# SWITCHES.net
KiCad netlist of a schematic drawn in Altium Designer
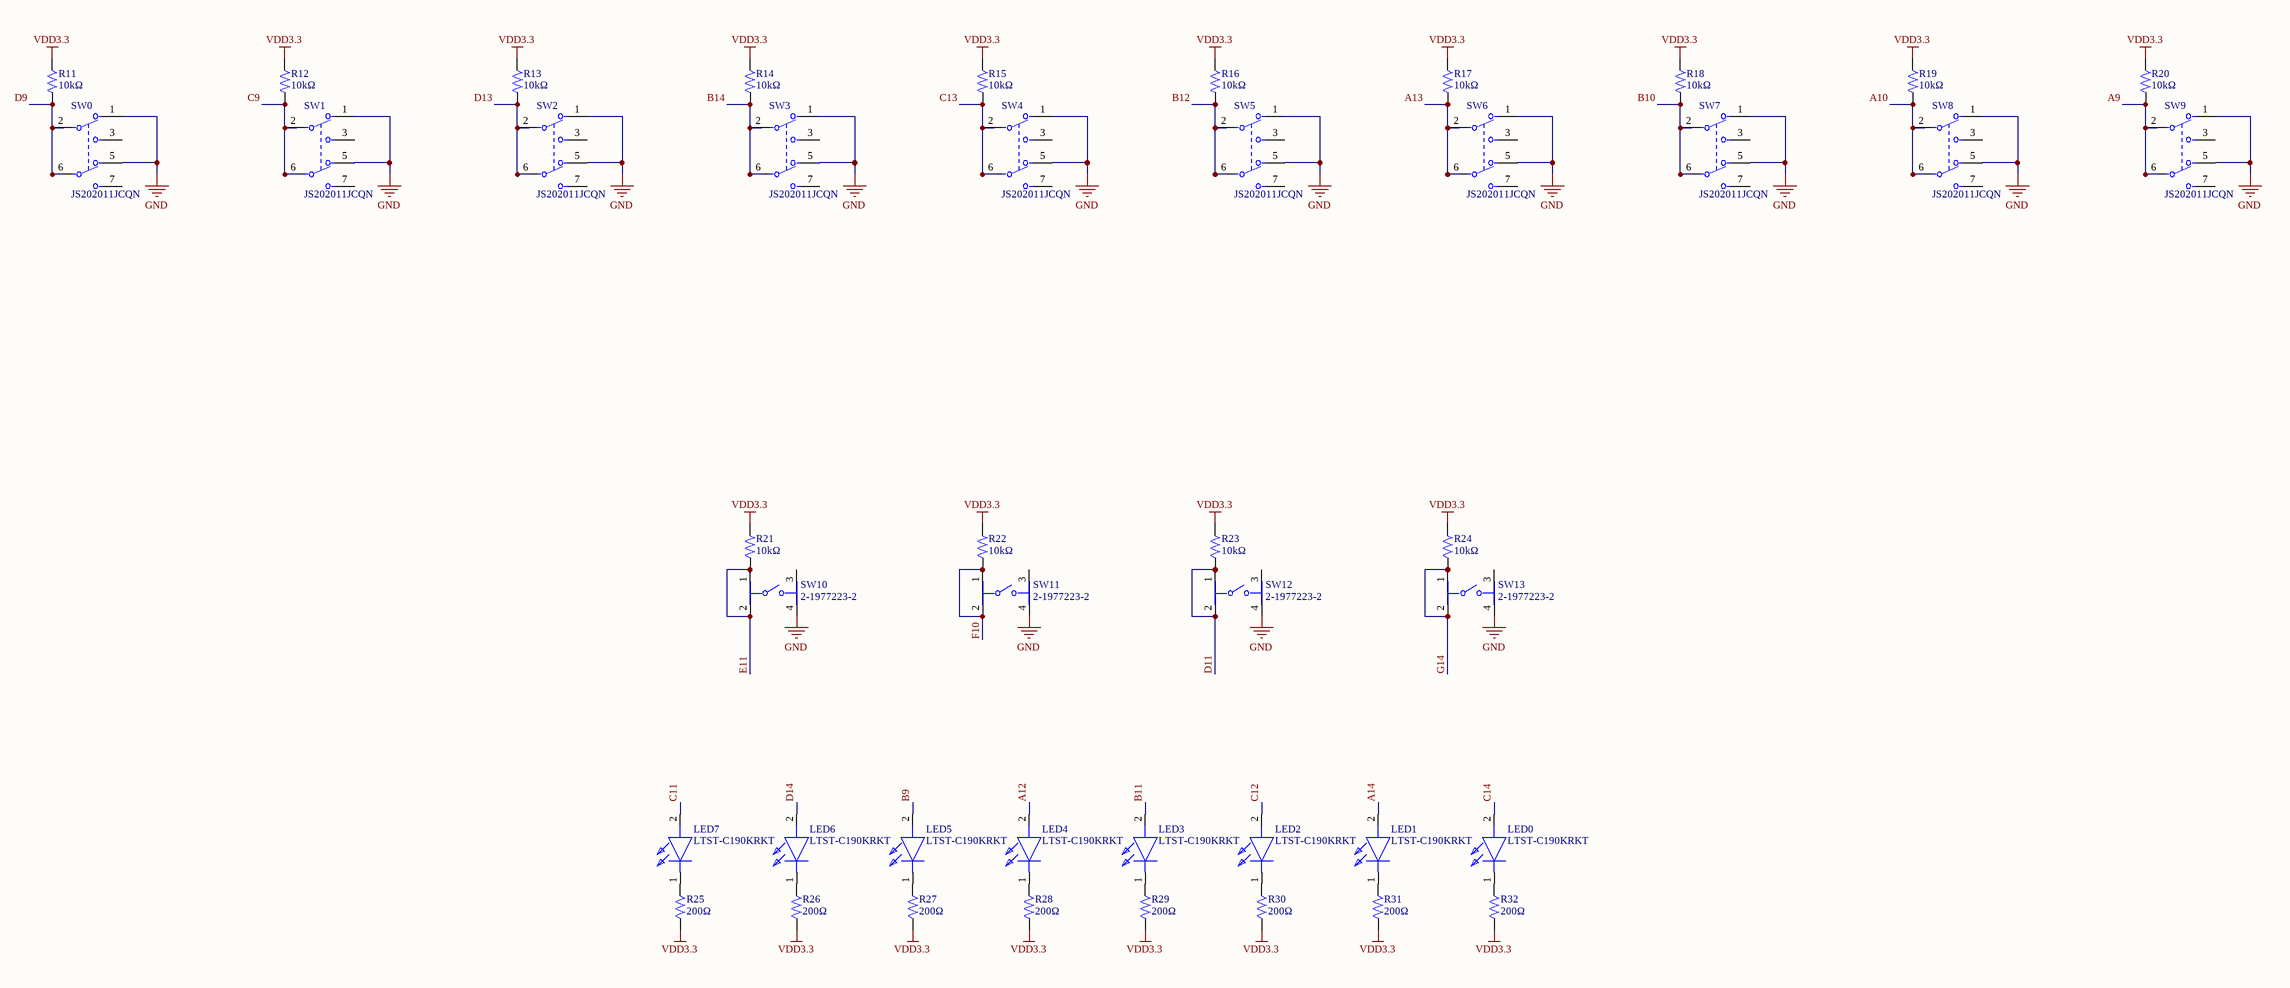
[diagram p0: SWITCHES.SchDoc]

(export (version "E")
  (design (tool "Eeschema 10.0.6"))
  (components
    (comp (ref "LED0")
      (value "LTST-C190KRKT")
      (footprint "SamacSys:LEDC1608X80N")
      (description "LED")
      (fields (field (name "MOUSER PART NUMBER") "859-LTST-C190KRKT"))
      (libsource (lib "*") (part "LTST-C190KRKT"))
    )
    (comp (ref "LED1")
      (value "LTST-C190KRKT")
      (footprint "SamacSys:LEDC1608X80N")
      (description "LED")
      (fields (field (name "MOUSER PART NUMBER") "859-LTST-C190KRKT"))
      (libsource (lib "*") (part "LTST-C190KRKT"))
    )
    (comp (ref "LED2")
      (value "LTST-C190KRKT")
      (footprint "SamacSys:LEDC1608X80N")
      (description "LED")
      (fields (field (name "MOUSER PART NUMBER") "859-LTST-C190KRKT"))
      (libsource (lib "*") (part "LTST-C190KRKT"))
    )
    (comp (ref "LED3")
      (value "LTST-C190KRKT")
      (footprint "SamacSys:LEDC1608X80N")
      (description "LED")
      (fields (field (name "MOUSER PART NUMBER") "859-LTST-C190KRKT"))
      (libsource (lib "*") (part "LTST-C190KRKT"))
    )
    (comp (ref "LED4")
      (value "LTST-C190KRKT")
      (footprint "SamacSys:LEDC1608X80N")
      (description "LED")
      (fields (field (name "MOUSER PART NUMBER") "859-LTST-C190KRKT"))
      (libsource (lib "*") (part "LTST-C190KRKT"))
    )
    (comp (ref "LED5")
      (value "LTST-C190KRKT")
      (footprint "SamacSys:LEDC1608X80N")
      (description "LED")
      (fields (field (name "MOUSER PART NUMBER") "859-LTST-C190KRKT"))
      (libsource (lib "*") (part "LTST-C190KRKT"))
    )
    (comp (ref "LED6")
      (value "LTST-C190KRKT")
      (footprint "SamacSys:LEDC1608X80N")
      (description "LED")
      (fields (field (name "MOUSER PART NUMBER") "859-LTST-C190KRKT"))
      (libsource (lib "*") (part "LTST-C190KRKT"))
    )
    (comp (ref "LED7")
      (value "LTST-C190KRKT")
      (footprint "SamacSys:LEDC1608X80N")
      (description "LED")
      (fields (field (name "MOUSER PART NUMBER") "859-LTST-C190KRKT"))
      (libsource (lib "*") (part "LTST-C190KRKT"))
    )
    (comp (ref "R11")
      (value "0603WAF1002T5E")
      (footprint "RES-0603")
      (description "Resistor, 10kΩ, ±1%, 100mW, 75V, ±100ppm/℃, -55℃~+155℃, SMD 0603")
      (fields
        (field (name "MANUFACTURER") "Uniroyal")
        (field (name "JLCPCB PART NUMBER") "C25804")
        (field (name "RESISTANCE") "10kΩ")
      )
      (libsource (lib "jlcpcb_2025_04_resistors_basic") (part "0603WAF1002T5E"))
    )
    (comp (ref "R12")
      (value "0603WAF1002T5E")
      (footprint "RES-0603")
      (description "Resistor, 10kΩ, ±1%, 100mW, 75V, ±100ppm/℃, -55℃~+155℃, SMD 0603")
      (fields
        (field (name "MANUFACTURER") "Uniroyal")
        (field (name "JLCPCB PART NUMBER") "C25804")
        (field (name "RESISTANCE") "10kΩ")
      )
      (libsource (lib "jlcpcb_2025_04_resistors_basic") (part "0603WAF1002T5E"))
    )
    (comp (ref "R13")
      (value "0603WAF1002T5E")
      (footprint "RES-0603")
      (description "Resistor, 10kΩ, ±1%, 100mW, 75V, ±100ppm/℃, -55℃~+155℃, SMD 0603")
      (fields
        (field (name "MANUFACTURER") "Uniroyal")
        (field (name "JLCPCB PART NUMBER") "C25804")
        (field (name "RESISTANCE") "10kΩ")
      )
      (libsource (lib "jlcpcb_2025_04_resistors_basic") (part "0603WAF1002T5E"))
    )
    (comp (ref "R14")
      (value "0603WAF1002T5E")
      (footprint "RES-0603")
      (description "Resistor, 10kΩ, ±1%, 100mW, 75V, ±100ppm/℃, -55℃~+155℃, SMD 0603")
      (fields
        (field (name "MANUFACTURER") "Uniroyal")
        (field (name "JLCPCB PART NUMBER") "C25804")
        (field (name "RESISTANCE") "10kΩ")
      )
      (libsource (lib "jlcpcb_2025_04_resistors_basic") (part "0603WAF1002T5E"))
    )
    (comp (ref "R15")
      (value "0603WAF1002T5E")
      (footprint "RES-0603")
      (description "Resistor, 10kΩ, ±1%, 100mW, 75V, ±100ppm/℃, -55℃~+155℃, SMD 0603")
      (fields
        (field (name "MANUFACTURER") "Uniroyal")
        (field (name "JLCPCB PART NUMBER") "C25804")
        (field (name "RESISTANCE") "10kΩ")
      )
      (libsource (lib "jlcpcb_2025_04_resistors_basic") (part "0603WAF1002T5E"))
    )
    (comp (ref "R16")
      (value "0603WAF1002T5E")
      (footprint "RES-0603")
      (description "Resistor, 10kΩ, ±1%, 100mW, 75V, ±100ppm/℃, -55℃~+155℃, SMD 0603")
      (fields
        (field (name "MANUFACTURER") "Uniroyal")
        (field (name "JLCPCB PART NUMBER") "C25804")
        (field (name "RESISTANCE") "10kΩ")
      )
      (libsource (lib "jlcpcb_2025_04_resistors_basic") (part "0603WAF1002T5E"))
    )
    (comp (ref "R17")
      (value "0603WAF1002T5E")
      (footprint "RES-0603")
      (description "Resistor, 10kΩ, ±1%, 100mW, 75V, ±100ppm/℃, -55℃~+155℃, SMD 0603")
      (fields
        (field (name "MANUFACTURER") "Uniroyal")
        (field (name "JLCPCB PART NUMBER") "C25804")
        (field (name "RESISTANCE") "10kΩ")
      )
      (libsource (lib "jlcpcb_2025_04_resistors_basic") (part "0603WAF1002T5E"))
    )
    (comp (ref "R18")
      (value "0603WAF1002T5E")
      (footprint "RES-0603")
      (description "Resistor, 10kΩ, ±1%, 100mW, 75V, ±100ppm/℃, -55℃~+155℃, SMD 0603")
      (fields
        (field (name "MANUFACTURER") "Uniroyal")
        (field (name "JLCPCB PART NUMBER") "C25804")
        (field (name "RESISTANCE") "10kΩ")
      )
      (libsource (lib "jlcpcb_2025_04_resistors_basic") (part "0603WAF1002T5E"))
    )
    (comp (ref "R19")
      (value "0603WAF1002T5E")
      (footprint "RES-0603")
      (description "Resistor, 10kΩ, ±1%, 100mW, 75V, ±100ppm/℃, -55℃~+155℃, SMD 0603")
      (fields
        (field (name "MANUFACTURER") "Uniroyal")
        (field (name "JLCPCB PART NUMBER") "C25804")
        (field (name "RESISTANCE") "10kΩ")
      )
      (libsource (lib "jlcpcb_2025_04_resistors_basic") (part "0603WAF1002T5E"))
    )
    (comp (ref "R20")
      (value "0603WAF1002T5E")
      (footprint "RES-0603")
      (description "Resistor, 10kΩ, ±1%, 100mW, 75V, ±100ppm/℃, -55℃~+155℃, SMD 0603")
      (fields
        (field (name "MANUFACTURER") "Uniroyal")
        (field (name "JLCPCB PART NUMBER") "C25804")
        (field (name "RESISTANCE") "10kΩ")
      )
      (libsource (lib "jlcpcb_2025_04_resistors_basic") (part "0603WAF1002T5E"))
    )
    (comp (ref "R21")
      (value "0603WAF1002T5E")
      (footprint "RES-0603")
      (description "Resistor, 10kΩ, ±1%, 100mW, 75V, ±100ppm/℃, -55℃~+155℃, SMD 0603")
      (fields
        (field (name "MANUFACTURER") "Uniroyal")
        (field (name "JLCPCB PART NUMBER") "C25804")
        (field (name "RESISTANCE") "10kΩ")
      )
      (libsource (lib "jlcpcb_2025_04_resistors_basic") (part "0603WAF1002T5E"))
    )
    (comp (ref "R22")
      (value "0603WAF1002T5E")
      (footprint "RES-0603")
      (description "Resistor, 10kΩ, ±1%, 100mW, 75V, ±100ppm/℃, -55℃~+155℃, SMD 0603")
      (fields
        (field (name "MANUFACTURER") "Uniroyal")
        (field (name "JLCPCB PART NUMBER") "C25804")
        (field (name "RESISTANCE") "10kΩ")
      )
      (libsource (lib "jlcpcb_2025_04_resistors_basic") (part "0603WAF1002T5E"))
    )
    (comp (ref "R23")
      (value "0603WAF1002T5E")
      (footprint "RES-0603")
      (description "Resistor, 10kΩ, ±1%, 100mW, 75V, ±100ppm/℃, -55℃~+155℃, SMD 0603")
      (fields
        (field (name "MANUFACTURER") "Uniroyal")
        (field (name "JLCPCB PART NUMBER") "C25804")
        (field (name "RESISTANCE") "10kΩ")
      )
      (libsource (lib "jlcpcb_2025_04_resistors_basic") (part "0603WAF1002T5E"))
    )
    (comp (ref "R24")
      (value "0603WAF1002T5E")
      (footprint "RES-0603")
      (description "Resistor, 10kΩ, ±1%, 100mW, 75V, ±100ppm/℃, -55℃~+155℃, SMD 0603")
      (fields
        (field (name "MANUFACTURER") "Uniroyal")
        (field (name "JLCPCB PART NUMBER") "C25804")
        (field (name "RESISTANCE") "10kΩ")
      )
      (libsource (lib "jlcpcb_2025_04_resistors_basic") (part "0603WAF1002T5E"))
    )
    (comp (ref "R25")
      (value "0402WGF2000TCE")
      (footprint "RES-0402")
      (description "Resistor, 200Ω, ±1%, 62.5mW, 50V, ±100ppm/℃, -55℃~+155℃, SMD 0402")
      (fields
        (field (name "MANUFACTURER") "Uniroyal")
        (field (name "JLCPCB PART NUMBER") "C25087")
        (field (name "RESISTANCE") "200Ω")
      )
      (libsource (lib "jlcpcb_2025_04_resistors_basic") (part "0402WGF2000TCE"))
    )
    (comp (ref "R26")
      (value "0402WGF2000TCE")
      (footprint "RES-0402")
      (description "Resistor, 200Ω, ±1%, 62.5mW, 50V, ±100ppm/℃, -55℃~+155℃, SMD 0402")
      (fields
        (field (name "MANUFACTURER") "Uniroyal")
        (field (name "JLCPCB PART NUMBER") "C25087")
        (field (name "RESISTANCE") "200Ω")
      )
      (libsource (lib "jlcpcb_2025_04_resistors_basic") (part "0402WGF2000TCE"))
    )
    (comp (ref "R27")
      (value "0402WGF2000TCE")
      (footprint "RES-0402")
      (description "Resistor, 200Ω, ±1%, 62.5mW, 50V, ±100ppm/℃, -55℃~+155℃, SMD 0402")
      (fields
        (field (name "MANUFACTURER") "Uniroyal")
        (field (name "JLCPCB PART NUMBER") "C25087")
        (field (name "RESISTANCE") "200Ω")
      )
      (libsource (lib "jlcpcb_2025_04_resistors_basic") (part "0402WGF2000TCE"))
    )
    (comp (ref "R28")
      (value "0402WGF2000TCE")
      (footprint "RES-0402")
      (description "Resistor, 200Ω, ±1%, 62.5mW, 50V, ±100ppm/℃, -55℃~+155℃, SMD 0402")
      (fields
        (field (name "MANUFACTURER") "Uniroyal")
        (field (name "JLCPCB PART NUMBER") "C25087")
        (field (name "RESISTANCE") "200Ω")
      )
      (libsource (lib "jlcpcb_2025_04_resistors_basic") (part "0402WGF2000TCE"))
    )
    (comp (ref "R29")
      (value "0402WGF2000TCE")
      (footprint "RES-0402")
      (description "Resistor, 200Ω, ±1%, 62.5mW, 50V, ±100ppm/℃, -55℃~+155℃, SMD 0402")
      (fields
        (field (name "MANUFACTURER") "Uniroyal")
        (field (name "JLCPCB PART NUMBER") "C25087")
        (field (name "RESISTANCE") "200Ω")
      )
      (libsource (lib "jlcpcb_2025_04_resistors_basic") (part "0402WGF2000TCE"))
    )
    (comp (ref "R30")
      (value "0402WGF2000TCE")
      (footprint "RES-0402")
      (description "Resistor, 200Ω, ±1%, 62.5mW, 50V, ±100ppm/℃, -55℃~+155℃, SMD 0402")
      (fields
        (field (name "MANUFACTURER") "Uniroyal")
        (field (name "JLCPCB PART NUMBER") "C25087")
        (field (name "RESISTANCE") "200Ω")
      )
      (libsource (lib "jlcpcb_2025_04_resistors_basic") (part "0402WGF2000TCE"))
    )
    (comp (ref "R31")
      (value "0402WGF2000TCE")
      (footprint "RES-0402")
      (description "Resistor, 200Ω, ±1%, 62.5mW, 50V, ±100ppm/℃, -55℃~+155℃, SMD 0402")
      (fields
        (field (name "MANUFACTURER") "Uniroyal")
        (field (name "JLCPCB PART NUMBER") "C25087")
        (field (name "RESISTANCE") "200Ω")
      )
      (libsource (lib "jlcpcb_2025_04_resistors_basic") (part "0402WGF2000TCE"))
    )
    (comp (ref "R32")
      (value "0402WGF2000TCE")
      (footprint "RES-0402")
      (description "Resistor, 200Ω, ±1%, 62.5mW, 50V, ±100ppm/℃, -55℃~+155℃, SMD 0402")
      (fields
        (field (name "MANUFACTURER") "Uniroyal")
        (field (name "JLCPCB PART NUMBER") "C25087")
        (field (name "RESISTANCE") "200Ω")
      )
      (libsource (lib "jlcpcb_2025_04_resistors_basic") (part "0402WGF2000TCE"))
    )
    (comp (ref "SW0")
      (value "JS202011JCQN")
      (footprint "FP-JS202011JCQN-MFG")
      (description "SWITCH SLIDE DPDT 300MA 6V")
      (libsource (lib "Altium Content Vault") (part "6b3bc4f94d389b2e45f6181d1f21823"))
    )
    (comp (ref "SW1")
      (value "JS202011JCQN")
      (footprint "FP-JS202011JCQN-MFG")
      (description "SWITCH SLIDE DPDT 300MA 6V")
      (libsource (lib "Altium Content Vault") (part "6b3bc4f94d389b2e45f6181d1f21823"))
    )
    (comp (ref "SW2")
      (value "JS202011JCQN")
      (footprint "FP-JS202011JCQN-MFG")
      (description "SWITCH SLIDE DPDT 300MA 6V")
      (libsource (lib "Altium Content Vault") (part "6b3bc4f94d389b2e45f6181d1f21823"))
    )
    (comp (ref "SW3")
      (value "JS202011JCQN")
      (footprint "FP-JS202011JCQN-MFG")
      (description "SWITCH SLIDE DPDT 300MA 6V")
      (libsource (lib "Altium Content Vault") (part "6b3bc4f94d389b2e45f6181d1f21823"))
    )
    (comp (ref "SW4")
      (value "JS202011JCQN")
      (footprint "FP-JS202011JCQN-MFG")
      (description "SWITCH SLIDE DPDT 300MA 6V")
      (libsource (lib "Altium Content Vault") (part "6b3bc4f94d389b2e45f6181d1f21823"))
    )
    (comp (ref "SW5")
      (value "JS202011JCQN")
      (footprint "FP-JS202011JCQN-MFG")
      (description "SWITCH SLIDE DPDT 300MA 6V")
      (libsource (lib "Altium Content Vault") (part "6b3bc4f94d389b2e45f6181d1f21823"))
    )
    (comp (ref "SW6")
      (value "JS202011JCQN")
      (footprint "FP-JS202011JCQN-MFG")
      (description "SWITCH SLIDE DPDT 300MA 6V")
      (libsource (lib "Altium Content Vault") (part "6b3bc4f94d389b2e45f6181d1f21823"))
    )
    (comp (ref "SW7")
      (value "JS202011JCQN")
      (footprint "FP-JS202011JCQN-MFG")
      (description "SWITCH SLIDE DPDT 300MA 6V")
      (libsource (lib "Altium Content Vault") (part "6b3bc4f94d389b2e45f6181d1f21823"))
    )
    (comp (ref "SW8")
      (value "JS202011JCQN")
      (footprint "FP-JS202011JCQN-MFG")
      (description "SWITCH SLIDE DPDT 300MA 6V")
      (libsource (lib "Altium Content Vault") (part "6b3bc4f94d389b2e45f6181d1f21823"))
    )
    (comp (ref "SW9")
      (value "JS202011JCQN")
      (footprint "FP-JS202011JCQN-MFG")
      (description "SWITCH SLIDE DPDT 300MA 6V")
      (libsource (lib "Altium Content Vault") (part "6b3bc4f94d389b2e45f6181d1f21823"))
    )
    (comp (ref "SW10")
      (value "2-1977223-2")
      (footprint "FP-2-1977223-2-MFG")
      (description "SWITCH TACTILE SPST-NO 0.05A 24V")
      (libsource (lib "Altium Content Vault") (part "b8895f3f4cefb76e1819d2863dba89b"))
    )
    (comp (ref "SW11")
      (value "2-1977223-2")
      (footprint "FP-2-1977223-2-MFG")
      (description "SWITCH TACTILE SPST-NO 0.05A 24V")
      (libsource (lib "Altium Content Vault") (part "b8895f3f4cefb76e1819d2863dba89b"))
    )
    (comp (ref "SW12")
      (value "2-1977223-2")
      (footprint "FP-2-1977223-2-MFG")
      (description "SWITCH TACTILE SPST-NO 0.05A 24V")
      (libsource (lib "Altium Content Vault") (part "b8895f3f4cefb76e1819d2863dba89b"))
    )
    (comp (ref "SW13")
      (value "2-1977223-2")
      (footprint "FP-2-1977223-2-MFG")
      (description "SWITCH TACTILE SPST-NO 0.05A 24V")
      (libsource (lib "Altium Content Vault") (part "b8895f3f4cefb76e1819d2863dba89b"))
    )
  )
  (nets
    (net (code "1") (name "/A9") (class "Default")
      (node (ref "R20") (pin "1") (pinfunction "1_1") (pintype "passive"))
      (node (ref "SW9") (pin "2") (pinfunction "1_C_2") (pintype "passive"))
      (node (ref "SW9") (pin "6") (pinfunction "2_C_6") (pintype "passive"))
    )
    (net (code "2") (name "/A10") (class "Default")
      (node (ref "R19") (pin "1") (pinfunction "1_1") (pintype "passive"))
      (node (ref "SW8") (pin "2") (pinfunction "1_C_2") (pintype "passive"))
      (node (ref "SW8") (pin "6") (pinfunction "2_C_6") (pintype "passive"))
    )
    (net (code "3") (name "/A12") (class "Default")
      (node (ref "LED4") (pin "2") (pinfunction "A_2") (pintype "passive"))
    )
    (net (code "4") (name "/A13") (class "Default")
      (node (ref "R17") (pin "1") (pinfunction "1_1") (pintype "passive"))
      (node (ref "SW6") (pin "2") (pinfunction "1_C_2") (pintype "passive"))
      (node (ref "SW6") (pin "6") (pinfunction "2_C_6") (pintype "passive"))
    )
    (net (code "5") (name "/A14") (class "Default")
      (node (ref "LED1") (pin "2") (pinfunction "A_2") (pintype "passive"))
    )
    (net (code "6") (name "/B9") (class "Default")
      (node (ref "LED5") (pin "2") (pinfunction "A_2") (pintype "passive"))
    )
    (net (code "7") (name "/B10") (class "Default")
      (node (ref "R18") (pin "1") (pinfunction "1_1") (pintype "passive"))
      (node (ref "SW7") (pin "2") (pinfunction "1_C_2") (pintype "passive"))
      (node (ref "SW7") (pin "6") (pinfunction "2_C_6") (pintype "passive"))
    )
    (net (code "8") (name "/B11") (class "Default")
      (node (ref "LED3") (pin "2") (pinfunction "A_2") (pintype "passive"))
    )
    (net (code "9") (name "/B12") (class "Default")
      (node (ref "R16") (pin "1") (pinfunction "1_1") (pintype "passive"))
      (node (ref "SW5") (pin "2") (pinfunction "1_C_2") (pintype "passive"))
      (node (ref "SW5") (pin "6") (pinfunction "2_C_6") (pintype "passive"))
    )
    (net (code "10") (name "/B14") (class "Default")
      (node (ref "R14") (pin "1") (pinfunction "1_1") (pintype "passive"))
      (node (ref "SW3") (pin "2") (pinfunction "1_C_2") (pintype "passive"))
      (node (ref "SW3") (pin "6") (pinfunction "2_C_6") (pintype "passive"))
    )
    (net (code "11") (name "/C9") (class "Default")
      (node (ref "R12") (pin "1") (pinfunction "1_1") (pintype "passive"))
      (node (ref "SW1") (pin "2") (pinfunction "1_C_2") (pintype "passive"))
      (node (ref "SW1") (pin "6") (pinfunction "2_C_6") (pintype "passive"))
    )
    (net (code "12") (name "/C11") (class "Default")
      (node (ref "LED7") (pin "2") (pinfunction "A_2") (pintype "passive"))
    )
    (net (code "13") (name "/C12") (class "Default")
      (node (ref "LED2") (pin "2") (pinfunction "A_2") (pintype "passive"))
    )
    (net (code "14") (name "/C13") (class "Default")
      (node (ref "R15") (pin "1") (pinfunction "1_1") (pintype "passive"))
      (node (ref "SW4") (pin "2") (pinfunction "1_C_2") (pintype "passive"))
      (node (ref "SW4") (pin "6") (pinfunction "2_C_6") (pintype "passive"))
    )
    (net (code "15") (name "/C14") (class "Default")
      (node (ref "LED0") (pin "2") (pinfunction "A_2") (pintype "passive"))
    )
    (net (code "16") (name "/D9") (class "Default")
      (node (ref "R11") (pin "1") (pinfunction "1_1") (pintype "passive"))
      (node (ref "SW0") (pin "2") (pinfunction "1_C_2") (pintype "passive"))
      (node (ref "SW0") (pin "6") (pinfunction "2_C_6") (pintype "passive"))
    )
    (net (code "17") (name "/D11") (class "Default")
      (node (ref "R23") (pin "1") (pinfunction "1_1") (pintype "passive"))
      (node (ref "SW12") (pin "1") (pinfunction "1_1") (pintype "passive"))
      (node (ref "SW12") (pin "2") (pinfunction "2_2") (pintype "passive"))
    )
    (net (code "18") (name "/D13") (class "Default")
      (node (ref "R13") (pin "1") (pinfunction "1_1") (pintype "passive"))
      (node (ref "SW2") (pin "2") (pinfunction "1_C_2") (pintype "passive"))
      (node (ref "SW2") (pin "6") (pinfunction "2_C_6") (pintype "passive"))
    )
    (net (code "19") (name "/D14") (class "Default")
      (node (ref "LED6") (pin "2") (pinfunction "A_2") (pintype "passive"))
    )
    (net (code "20") (name "/E11") (class "Default")
      (node (ref "R21") (pin "1") (pinfunction "1_1") (pintype "passive"))
      (node (ref "SW10") (pin "1") (pinfunction "1_1") (pintype "passive"))
      (node (ref "SW10") (pin "2") (pinfunction "2_2") (pintype "passive"))
    )
    (net (code "21") (name "/F10") (class "Default")
      (node (ref "R22") (pin "1") (pinfunction "1_1") (pintype "passive"))
      (node (ref "SW11") (pin "1") (pinfunction "1_1") (pintype "passive"))
      (node (ref "SW11") (pin "2") (pinfunction "2_2") (pintype "passive"))
    )
    (net (code "22") (name "/G14") (class "Default")
      (node (ref "R24") (pin "1") (pinfunction "1_1") (pintype "passive"))
      (node (ref "SW13") (pin "1") (pinfunction "1_1") (pintype "passive"))
      (node (ref "SW13") (pin "2") (pinfunction "2_2") (pintype "passive"))
    )
    (net (code "23") (name "GND") (class "Default")
      (node (ref "SW0") (pin "1") (pinfunction "1_1") (pintype "passive"))
      (node (ref "SW0") (pin "5") (pinfunction "5_5") (pintype "passive"))
      (node (ref "SW1") (pin "1") (pinfunction "1_1") (pintype "passive"))
      (node (ref "SW1") (pin "5") (pinfunction "5_5") (pintype "passive"))
      (node (ref "SW10") (pin "4") (pinfunction "4_4") (pintype "passive"))
      (node (ref "SW11") (pin "4") (pinfunction "4_4") (pintype "passive"))
      (node (ref "SW12") (pin "4") (pinfunction "4_4") (pintype "passive"))
      (node (ref "SW13") (pin "4") (pinfunction "4_4") (pintype "passive"))
      (node (ref "SW2") (pin "1") (pinfunction "1_1") (pintype "passive"))
      (node (ref "SW2") (pin "5") (pinfunction "5_5") (pintype "passive"))
      (node (ref "SW3") (pin "1") (pinfunction "1_1") (pintype "passive"))
      (node (ref "SW3") (pin "5") (pinfunction "5_5") (pintype "passive"))
      (node (ref "SW4") (pin "1") (pinfunction "1_1") (pintype "passive"))
      (node (ref "SW4") (pin "5") (pinfunction "5_5") (pintype "passive"))
      (node (ref "SW5") (pin "1") (pinfunction "1_1") (pintype "passive"))
      (node (ref "SW5") (pin "5") (pinfunction "5_5") (pintype "passive"))
      (node (ref "SW6") (pin "1") (pinfunction "1_1") (pintype "passive"))
      (node (ref "SW6") (pin "5") (pinfunction "5_5") (pintype "passive"))
      (node (ref "SW7") (pin "1") (pinfunction "1_1") (pintype "passive"))
      (node (ref "SW7") (pin "5") (pinfunction "5_5") (pintype "passive"))
      (node (ref "SW8") (pin "1") (pinfunction "1_1") (pintype "passive"))
      (node (ref "SW8") (pin "5") (pinfunction "5_5") (pintype "passive"))
      (node (ref "SW9") (pin "1") (pinfunction "1_1") (pintype "passive"))
      (node (ref "SW9") (pin "5") (pinfunction "5_5") (pintype "passive"))
    )
    (net (code "24") (name "Net-(LED0-K)") (class "Default")
      (node (ref "LED0") (pin "1") (pinfunction "K_1") (pintype "passive"))
      (node (ref "R32") (pin "2") (pinfunction "2_2") (pintype "passive"))
    )
    (net (code "25") (name "Net-(LED1-K)") (class "Default")
      (node (ref "LED1") (pin "1") (pinfunction "K_1") (pintype "passive"))
      (node (ref "R31") (pin "2") (pinfunction "2_2") (pintype "passive"))
    )
    (net (code "26") (name "Net-(LED2-K)") (class "Default")
      (node (ref "LED2") (pin "1") (pinfunction "K_1") (pintype "passive"))
      (node (ref "R30") (pin "2") (pinfunction "2_2") (pintype "passive"))
    )
    (net (code "27") (name "Net-(LED3-K)") (class "Default")
      (node (ref "LED3") (pin "1") (pinfunction "K_1") (pintype "passive"))
      (node (ref "R29") (pin "2") (pinfunction "2_2") (pintype "passive"))
    )
    (net (code "28") (name "Net-(LED4-K)") (class "Default")
      (node (ref "LED4") (pin "1") (pinfunction "K_1") (pintype "passive"))
      (node (ref "R28") (pin "2") (pinfunction "2_2") (pintype "passive"))
    )
    (net (code "29") (name "Net-(LED5-K)") (class "Default")
      (node (ref "LED5") (pin "1") (pinfunction "K_1") (pintype "passive"))
      (node (ref "R27") (pin "2") (pinfunction "2_2") (pintype "passive"))
    )
    (net (code "30") (name "Net-(LED6-K)") (class "Default")
      (node (ref "LED6") (pin "1") (pinfunction "K_1") (pintype "passive"))
      (node (ref "R26") (pin "2") (pinfunction "2_2") (pintype "passive"))
    )
    (net (code "31") (name "Net-(LED7-K)") (class "Default")
      (node (ref "LED7") (pin "1") (pinfunction "K_1") (pintype "passive"))
      (node (ref "R25") (pin "2") (pinfunction "2_2") (pintype "passive"))
    )
    (net (code "32") (name "VDD3.3") (class "Default")
      (node (ref "R11") (pin "2") (pinfunction "2_2") (pintype "passive"))
      (node (ref "R12") (pin "2") (pinfunction "2_2") (pintype "passive"))
      (node (ref "R13") (pin "2") (pinfunction "2_2") (pintype "passive"))
      (node (ref "R14") (pin "2") (pinfunction "2_2") (pintype "passive"))
      (node (ref "R15") (pin "2") (pinfunction "2_2") (pintype "passive"))
      (node (ref "R16") (pin "2") (pinfunction "2_2") (pintype "passive"))
      (node (ref "R17") (pin "2") (pinfunction "2_2") (pintype "passive"))
      (node (ref "R18") (pin "2") (pinfunction "2_2") (pintype "passive"))
      (node (ref "R19") (pin "2") (pinfunction "2_2") (pintype "passive"))
      (node (ref "R20") (pin "2") (pinfunction "2_2") (pintype "passive"))
      (node (ref "R21") (pin "2") (pinfunction "2_2") (pintype "passive"))
      (node (ref "R22") (pin "2") (pinfunction "2_2") (pintype "passive"))
      (node (ref "R23") (pin "2") (pinfunction "2_2") (pintype "passive"))
      (node (ref "R24") (pin "2") (pinfunction "2_2") (pintype "passive"))
      (node (ref "R25") (pin "1") (pinfunction "1_1") (pintype "passive"))
      (node (ref "R26") (pin "1") (pinfunction "1_1") (pintype "passive"))
      (node (ref "R27") (pin "1") (pinfunction "1_1") (pintype "passive"))
      (node (ref "R28") (pin "1") (pinfunction "1_1") (pintype "passive"))
      (node (ref "R29") (pin "1") (pinfunction "1_1") (pintype "passive"))
      (node (ref "R30") (pin "1") (pinfunction "1_1") (pintype "passive"))
      (node (ref "R31") (pin "1") (pinfunction "1_1") (pintype "passive"))
      (node (ref "R32") (pin "1") (pinfunction "1_1") (pintype "passive"))
    )
    (net (code "33") (name "unconnected-(SW0-Pad3)") (class "Default")
      (node (ref "SW0") (pin "3") (pinfunction "3_3") (pintype "passive"))
    )
    (net (code "34") (name "unconnected-(SW0-Pad7)") (class "Default")
      (node (ref "SW0") (pin "7") (pinfunction "7_7") (pintype "passive"))
    )
    (net (code "35") (name "unconnected-(SW1-Pad3)") (class "Default")
      (node (ref "SW1") (pin "3") (pinfunction "3_3") (pintype "passive"))
    )
    (net (code "36") (name "unconnected-(SW1-Pad7)") (class "Default")
      (node (ref "SW1") (pin "7") (pinfunction "7_7") (pintype "passive"))
    )
    (net (code "37") (name "unconnected-(SW2-Pad3)") (class "Default")
      (node (ref "SW2") (pin "3") (pinfunction "3_3") (pintype "passive"))
    )
    (net (code "38") (name "unconnected-(SW2-Pad7)") (class "Default")
      (node (ref "SW2") (pin "7") (pinfunction "7_7") (pintype "passive"))
    )
    (net (code "39") (name "unconnected-(SW3-Pad3)") (class "Default")
      (node (ref "SW3") (pin "3") (pinfunction "3_3") (pintype "passive"))
    )
    (net (code "40") (name "unconnected-(SW3-Pad7)") (class "Default")
      (node (ref "SW3") (pin "7") (pinfunction "7_7") (pintype "passive"))
    )
    (net (code "41") (name "unconnected-(SW4-Pad3)") (class "Default")
      (node (ref "SW4") (pin "3") (pinfunction "3_3") (pintype "passive"))
    )
    (net (code "42") (name "unconnected-(SW4-Pad7)") (class "Default")
      (node (ref "SW4") (pin "7") (pinfunction "7_7") (pintype "passive"))
    )
    (net (code "43") (name "unconnected-(SW5-Pad3)") (class "Default")
      (node (ref "SW5") (pin "3") (pinfunction "3_3") (pintype "passive"))
    )
    (net (code "44") (name "unconnected-(SW5-Pad7)") (class "Default")
      (node (ref "SW5") (pin "7") (pinfunction "7_7") (pintype "passive"))
    )
    (net (code "45") (name "unconnected-(SW6-Pad3)") (class "Default")
      (node (ref "SW6") (pin "3") (pinfunction "3_3") (pintype "passive"))
    )
    (net (code "46") (name "unconnected-(SW6-Pad7)") (class "Default")
      (node (ref "SW6") (pin "7") (pinfunction "7_7") (pintype "passive"))
    )
    (net (code "47") (name "unconnected-(SW7-Pad3)") (class "Default")
      (node (ref "SW7") (pin "3") (pinfunction "3_3") (pintype "passive"))
    )
    (net (code "48") (name "unconnected-(SW7-Pad7)") (class "Default")
      (node (ref "SW7") (pin "7") (pinfunction "7_7") (pintype "passive"))
    )
    (net (code "49") (name "unconnected-(SW8-Pad3)") (class "Default")
      (node (ref "SW8") (pin "3") (pinfunction "3_3") (pintype "passive"))
    )
    (net (code "50") (name "unconnected-(SW8-Pad7)") (class "Default")
      (node (ref "SW8") (pin "7") (pinfunction "7_7") (pintype "passive"))
    )
    (net (code "51") (name "unconnected-(SW9-Pad3)") (class "Default")
      (node (ref "SW9") (pin "3") (pinfunction "3_3") (pintype "passive"))
    )
    (net (code "52") (name "unconnected-(SW9-Pad7)") (class "Default")
      (node (ref "SW9") (pin "7") (pinfunction "7_7") (pintype "passive"))
    )
    (net (code "53") (name "unconnected-(SW10-Pad3)") (class "Default")
      (node (ref "SW10") (pin "3") (pinfunction "3_3") (pintype "passive"))
    )
    (net (code "54") (name "unconnected-(SW11-Pad3)") (class "Default")
      (node (ref "SW11") (pin "3") (pinfunction "3_3") (pintype "passive"))
    )
    (net (code "55") (name "unconnected-(SW12-Pad3)") (class "Default")
      (node (ref "SW12") (pin "3") (pinfunction "3_3") (pintype "passive"))
    )
    (net (code "56") (name "unconnected-(SW13-Pad3)") (class "Default")
      (node (ref "SW13") (pin "3") (pinfunction "3_3") (pintype "passive"))
    )
  )
)
